# LM7310.net
KiCad netlist of a schematic drawn in Altium Designer
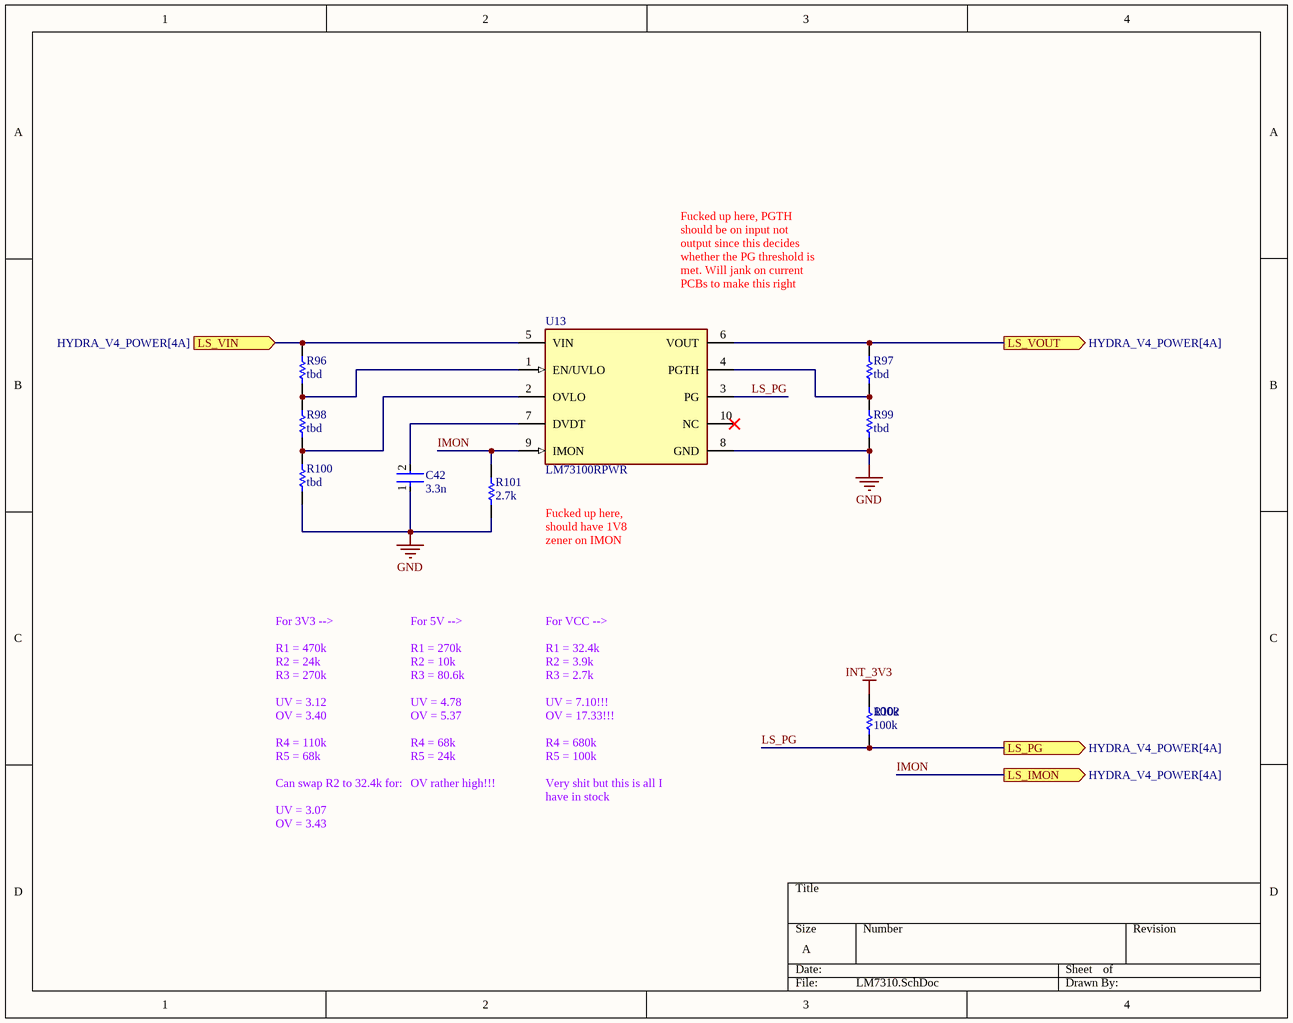
[diagram p0: LM7310.SchDoc]

(export (version "E")
  (design (tool "Eeschema 10.0.6"))
  (components
    (comp (ref "C42")
      (value "3.3n")
      (footprint "FP-0402-L_1_0_0_05-W_0_5-IPC_A")
      (description "LARGE PADS, 0402 CAP, CHANGE COMMENT TO MATCH REAL P/N")
      (libsource (lib "Space Concordia") (part "b4654b650e69147ec39a6b967a45e02"))
    )
    (comp (ref "R96")
      (value "tbd")
      (footprint "R0603B")
      (description "Resistor")
      (libsource (lib "Space Concordia") (part "Resistor"))
    )
    (comp (ref "R97")
      (value "tbd")
      (footprint "R0603B")
      (description "Resistor")
      (libsource (lib "Space Concordia") (part "Resistor"))
    )
    (comp (ref "R98")
      (value "tbd")
      (footprint "R0603B")
      (description "Resistor")
      (libsource (lib "Space Concordia") (part "Resistor"))
    )
    (comp (ref "R99")
      (value "tbd")
      (footprint "R0603B")
      (description "Resistor")
      (libsource (lib "Space Concordia") (part "Resistor"))
    )
    (comp (ref "R100")
      (value "tbd")
      (footprint "R0603B")
      (description "Resistor")
      (libsource (lib "Space Concordia") (part "Resistor"))
    )
    (comp (ref "R101")
      (value "2.7k")
      (footprint "R0603B")
      (description "Resistor")
      (libsource (lib "Space Concordia") (part "Resistor"))
    )
    (comp (ref "R102")
      (value "100k")
      (footprint "R0603B")
      (description "Resistor")
      (fields (field (name "ALTIUM_VALUE") "100k"))
      (libsource (lib "Space Concordia") (part "Resistor"))
    )
    (comp (ref "U13")
      (value "LM73100RPWR")
      (footprint "FP-RPW0010A-MFG")
      (description "2.7-V TO 23-V, 5.5-A IDEAL DIODE")
      (libsource (lib "Altium Content Vault") (part "9bae3feabc31c7b50585ebbf6266d53"))
    )
  )
  (nets
    (net (code "1") (name "/IMON") (class "Default")
      (node (ref "R101") (pin "2") (pinfunction "2_2") (pintype "passive"))
      (node (ref "U13") (pin "9") (pinfunction "IMON_9") (pintype "input"))
    )
    (net (code "2") (name "/LS_PG") (class "Default")
      (node (ref "R102") (pin "1") (pinfunction "1_1") (pintype "passive"))
      (node (ref "U13") (pin "3") (pinfunction "PG_3") (pintype "open_collector"))
    )
    (net (code "3") (name "/LS_VIN") (class "Default")
      (node (ref "R96") (pin "2") (pinfunction "2_2") (pintype "passive"))
      (node (ref "U13") (pin "5") (pinfunction "VIN_5") (pintype "power_in"))
    )
    (net (code "4") (name "/LS_VOUT") (class "Default")
      (node (ref "R97") (pin "2") (pinfunction "2_2") (pintype "passive"))
      (node (ref "U13") (pin "6") (pinfunction "VOUT_6") (pintype "passive"))
    )
    (net (code "5") (name "GND") (class "Default")
      (node (ref "C42") (pin "1") (pinfunction "1_1") (pintype "passive"))
      (node (ref "R100") (pin "1") (pinfunction "1_1") (pintype "passive"))
      (node (ref "R101") (pin "1") (pinfunction "1_1") (pintype "passive"))
      (node (ref "R99") (pin "1") (pinfunction "1_1") (pintype "passive"))
      (node (ref "U13") (pin "8") (pinfunction "GND_8") (pintype "power_in"))
    )
    (net (code "6") (name "INT_3V3") (class "Default")
      (node (ref "R102") (pin "2") (pinfunction "2_2") (pintype "passive"))
    )
    (net (code "7") (name "Net-(U13-DVDT)") (class "Default")
      (node (ref "C42") (pin "2") (pinfunction "2_2") (pintype "passive"))
      (node (ref "U13") (pin "7") (pinfunction "DVDT_7") (pintype "passive"))
    )
    (net (code "8") (name "Net-(U13-EN{slash}UVLO)") (class "Default")
      (node (ref "R96") (pin "1") (pinfunction "1_1") (pintype "passive"))
      (node (ref "R98") (pin "2") (pinfunction "2_2") (pintype "passive"))
      (node (ref "U13") (pin "1") (pinfunction "EN/UVLO_1") (pintype "input"))
    )
    (net (code "9") (name "Net-(U13-OVLO)") (class "Default")
      (node (ref "R100") (pin "2") (pinfunction "2_2") (pintype "passive"))
      (node (ref "R98") (pin "1") (pinfunction "1_1") (pintype "passive"))
      (node (ref "U13") (pin "2") (pinfunction "OVLO_2") (pintype "passive"))
    )
    (net (code "10") (name "Net-(U13-PGTH)") (class "Default")
      (node (ref "R97") (pin "1") (pinfunction "1_1") (pintype "passive"))
      (node (ref "R99") (pin "2") (pinfunction "2_2") (pintype "passive"))
      (node (ref "U13") (pin "4") (pinfunction "PGTH_4") (pintype "passive"))
    )
    (net (code "11") (name "unconnected-(U13-NC-Pad10)") (class "Default")
      (node (ref "U13") (pin "10") (pinfunction "NC_10") (pintype "passive+no_connect"))
    )
  )
)
